# sch.net
KiCad netlist of a schematic drawn in Altium Designer
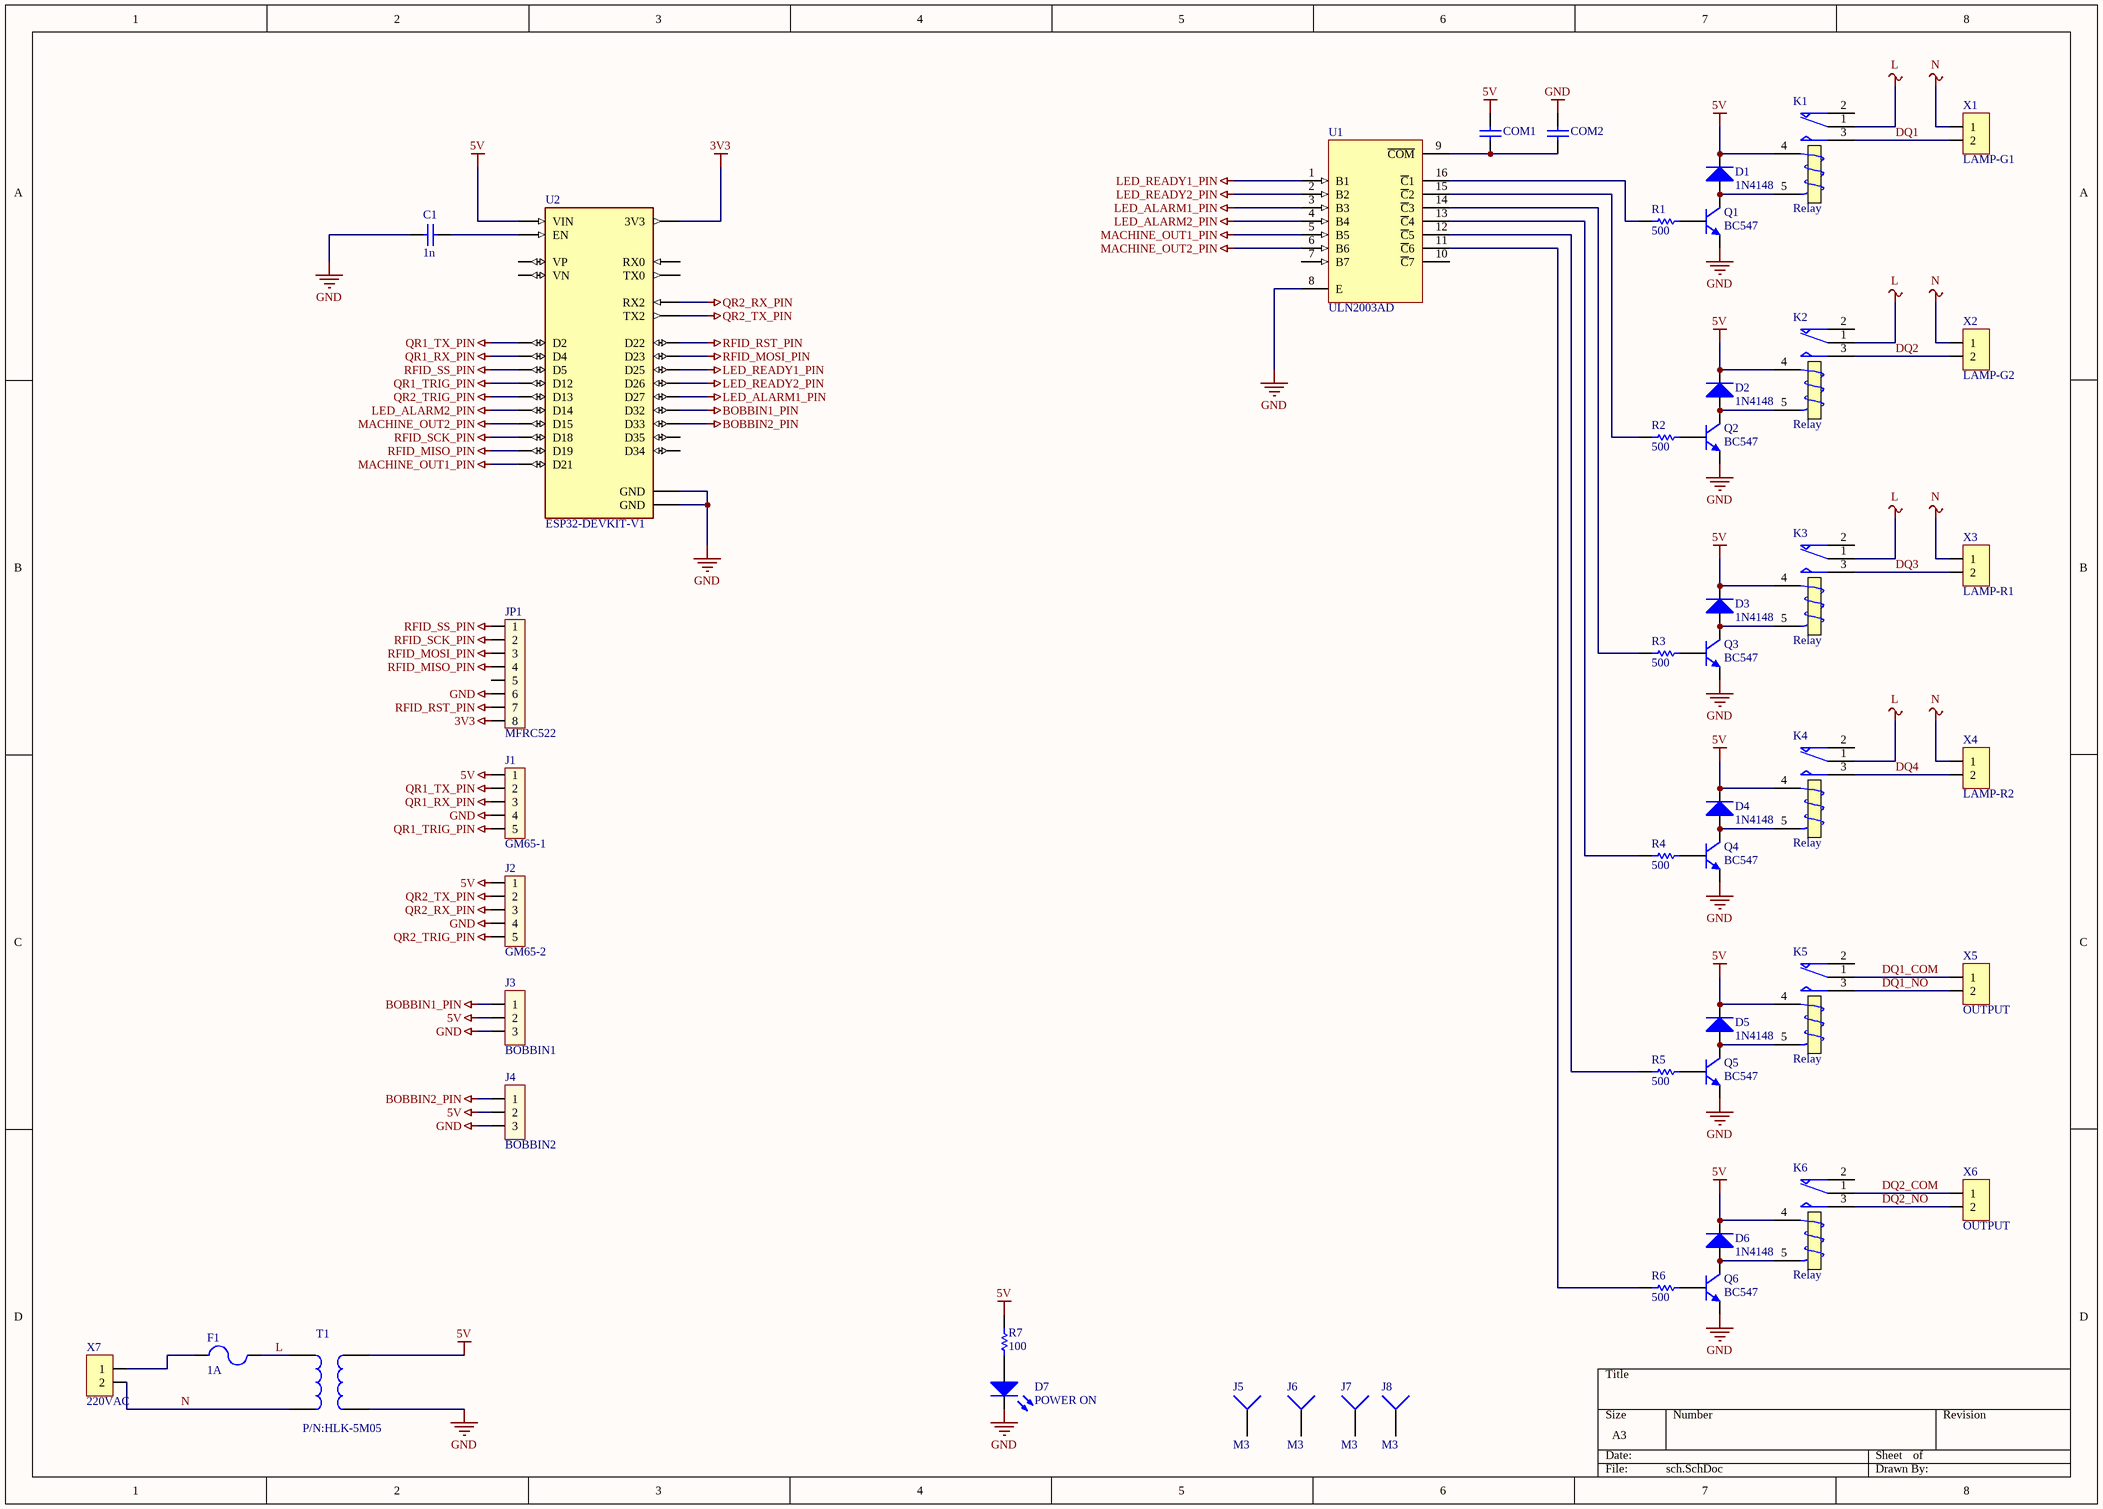
[diagram p0: sch.SchDoc]

(export (version "E")
  (design (tool "Eeschema 10.0.6"))
  (components
    (comp (ref "C1")
      (value "1n")
      (footprint "CR2012-0805")
      (description "Capacitor")
      (fields (field (name "PUBLISHER") "Altium Limited"))
      (libsource (lib "Miscellaneous Devices") (part "Cap"))
    )
    (comp (ref "COM1")
      (value "~")
      (footprint "CR2012-0805")
      (description "Capacitor")
      (fields (field (name "PUBLISHER") "Altium Limited"))
      (libsource (lib "Miscellaneous Devices") (part "Cap"))
    )
    (comp (ref "COM2")
      (value "~")
      (footprint "CR2012-0805")
      (description "Capacitor")
      (fields (field (name "PUBLISHER") "Altium Limited"))
      (libsource (lib "Miscellaneous Devices") (part "Cap"))
    )
    (comp (ref "D1")
      (value "1N4148")
      (footprint "D4148")
      (description "Default Diode")
      (fields (field (name "PUBLISHER") "Altium Limited"))
      (libsource (lib "weerachai") (part "Diode"))
    )
    (comp (ref "D2")
      (value "1N4148")
      (footprint "D4148")
      (description "Default Diode")
      (fields (field (name "PUBLISHER") "Altium Limited"))
      (libsource (lib "weerachai") (part "Diode"))
    )
    (comp (ref "D3")
      (value "1N4148")
      (footprint "D4148")
      (description "Default Diode")
      (fields (field (name "PUBLISHER") "Altium Limited"))
      (libsource (lib "weerachai") (part "Diode"))
    )
    (comp (ref "D4")
      (value "1N4148")
      (footprint "D4148")
      (description "Default Diode")
      (fields (field (name "PUBLISHER") "Altium Limited"))
      (libsource (lib "weerachai") (part "Diode"))
    )
    (comp (ref "D5")
      (value "1N4148")
      (footprint "D4148")
      (description "Default Diode")
      (fields (field (name "PUBLISHER") "Altium Limited"))
      (libsource (lib "weerachai") (part "Diode"))
    )
    (comp (ref "D6")
      (value "1N4148")
      (footprint "D4148")
      (description "Default Diode")
      (fields (field (name "PUBLISHER") "Altium Limited"))
      (libsource (lib "weerachai") (part "Diode"))
    )
    (comp (ref "D7")
      (value "POWER ON")
      (footprint "LED")
      (description "Typical INFRARED GaAs LED")
      (fields (field (name "PUBLISHER") "Altium Limited"))
      (libsource (lib "weerachai") (part "LED0"))
    )
    (comp (ref "F1")
      (value "1A")
      (footprint "CAP5W")
      (description "Fuse")
      (fields (field (name "PUBLISHER") "Altium Limited"))
      (libsource (lib "weerachai") (part "Fuse 2"))
    )
    (comp (ref "J1") (value "GM65-1") (footprint "XH2.54-5P") (libsource (lib "My Library") (part "JP5")))
    (comp (ref "J2") (value "GM65-2") (footprint "XH2.54-5P") (libsource (lib "My Library") (part "JP5")))
    (comp (ref "J3")
      (value "BOBBIN1")
      (footprint "XH2.54-3P")
      (description "Jumper 3")
      (libsource (lib "My Library") (part "JP3"))
    )
    (comp (ref "J4")
      (value "BOBBIN2")
      (footprint "XH2.54-3P")
      (description "Jumper 3")
      (libsource (lib "My Library") (part "JP3"))
    )
    (comp (ref "J5")
      (value "M3")
      (footprint "PAD")
      (description "Socket")
      (fields (field (name "PUBLISHER") "Altium Limited"))
      (libsource (lib "weerachai") (part "Socket"))
    )
    (comp (ref "J6")
      (value "M3")
      (footprint "PAD")
      (description "Socket")
      (fields (field (name "PUBLISHER") "Altium Limited"))
      (libsource (lib "weerachai") (part "Socket"))
    )
    (comp (ref "J7")
      (value "M3")
      (footprint "PAD")
      (description "Socket")
      (fields (field (name "PUBLISHER") "Altium Limited"))
      (libsource (lib "weerachai") (part "Socket"))
    )
    (comp (ref "J8")
      (value "M3")
      (footprint "PAD")
      (description "Socket")
      (fields (field (name "PUBLISHER") "Altium Limited"))
      (libsource (lib "weerachai") (part "Socket"))
    )
    (comp (ref "JP1")
      (value "MFRC522")
      (footprint "SIP8")
      (description "JP8 PIN")
      (libsource (lib "My Library") (part "JP8"))
    )
    (comp (ref "K1")
      (value "Relay")
      (footprint "RELAY1CON_REV")
      (description "SPDT Relay")
      (fields (field (name "PUBLISHER") "Altium Limited"))
      (libsource (lib "weerachai") (part "Relay"))
    )
    (comp (ref "K2")
      (value "Relay")
      (footprint "RELAY1CON_REV")
      (description "SPDT Relay")
      (fields (field (name "PUBLISHER") "Altium Limited"))
      (libsource (lib "weerachai") (part "Relay"))
    )
    (comp (ref "K3")
      (value "Relay")
      (footprint "RELAY1CON_REV")
      (description "SPDT Relay")
      (fields (field (name "PUBLISHER") "Altium Limited"))
      (libsource (lib "weerachai") (part "Relay"))
    )
    (comp (ref "K4")
      (value "Relay")
      (footprint "RELAY1CON_REV")
      (description "SPDT Relay")
      (fields (field (name "PUBLISHER") "Altium Limited"))
      (libsource (lib "weerachai") (part "Relay"))
    )
    (comp (ref "K5")
      (value "Relay")
      (footprint "RELAY1CON_REV")
      (description "SPDT Relay")
      (fields (field (name "PUBLISHER") "Altium Limited"))
      (libsource (lib "weerachai") (part "Relay"))
    )
    (comp (ref "K6")
      (value "Relay")
      (footprint "RELAY1CON_REV")
      (description "SPDT Relay")
      (fields (field (name "PUBLISHER") "Altium Limited"))
      (libsource (lib "weerachai") (part "Relay"))
    )
    (comp (ref "Q1")
      (value "BC547")
      (footprint "TO-92")
      (description "NPN General Purpose Amplifier")
      (fields (field (name "PUBLISHER") "Altium Limited"))
      (libsource (lib "weerachai") (part "2N3904"))
    )
    (comp (ref "Q2")
      (value "BC547")
      (footprint "TO-92")
      (description "NPN General Purpose Amplifier")
      (fields (field (name "PUBLISHER") "Altium Limited"))
      (libsource (lib "weerachai") (part "2N3904"))
    )
    (comp (ref "Q3")
      (value "BC547")
      (footprint "TO-92")
      (description "NPN General Purpose Amplifier")
      (fields (field (name "PUBLISHER") "Altium Limited"))
      (libsource (lib "weerachai") (part "2N3904"))
    )
    (comp (ref "Q4")
      (value "BC547")
      (footprint "TO-92")
      (description "NPN General Purpose Amplifier")
      (fields (field (name "PUBLISHER") "Altium Limited"))
      (libsource (lib "weerachai") (part "2N3904"))
    )
    (comp (ref "Q5")
      (value "BC547")
      (footprint "TO-92")
      (description "NPN General Purpose Amplifier")
      (fields (field (name "PUBLISHER") "Altium Limited"))
      (libsource (lib "weerachai") (part "2N3904"))
    )
    (comp (ref "Q6")
      (value "BC547")
      (footprint "TO-92")
      (description "NPN General Purpose Amplifier")
      (fields (field (name "PUBLISHER") "Altium Limited"))
      (libsource (lib "weerachai") (part "2N3904"))
    )
    (comp (ref "R1")
      (value "500")
      (footprint "R1/8")
      (description "Resistor")
      (fields (field (name "PUBLISHER") "Altium Limited"))
      (libsource (lib "weerachai") (part "Res1"))
    )
    (comp (ref "R2")
      (value "500")
      (footprint "R1/8")
      (description "Resistor")
      (fields (field (name "PUBLISHER") "Altium Limited"))
      (libsource (lib "weerachai") (part "Res1"))
    )
    (comp (ref "R3")
      (value "500")
      (footprint "R1/8")
      (description "Resistor")
      (fields (field (name "PUBLISHER") "Altium Limited"))
      (libsource (lib "weerachai") (part "Res1"))
    )
    (comp (ref "R4")
      (value "500")
      (footprint "R1/8")
      (description "Resistor")
      (fields (field (name "PUBLISHER") "Altium Limited"))
      (libsource (lib "weerachai") (part "Res1"))
    )
    (comp (ref "R5")
      (value "500")
      (footprint "R1/8")
      (description "Resistor")
      (fields (field (name "PUBLISHER") "Altium Limited"))
      (libsource (lib "weerachai") (part "Res1"))
    )
    (comp (ref "R6")
      (value "500")
      (footprint "R1/8")
      (description "Resistor")
      (fields (field (name "PUBLISHER") "Altium Limited"))
      (libsource (lib "weerachai") (part "Res1"))
    )
    (comp (ref "R7")
      (value "100")
      (footprint "R1/8")
      (description "Resistor")
      (fields (field (name "PUBLISHER") "Altium Limited"))
      (libsource (lib "weerachai") (part "Res1"))
    )
    (comp (ref "T1")
      (value "P/N:HLK-5M05")
      (footprint "HLK-PM01")
      (description "Transformer")
      (fields (field (name "PUBLISHER") "Altium Limited"))
      (libsource (lib "weerachai") (part "Trans"))
    )
    (comp (ref "U1")
      (value "ULN2003AD")
      (footprint "D016_N")
      (description "Darlington Transistor Array")
      (fields (field (name "PUBLISHER") "Altium Limited"))
      (libsource (lib "TI Interface Darlington Driver") (part "ULN2003AD"))
    )
    (comp (ref "U2")
      (value "ESP32-DEVKIT-V1")
      (footprint "ESP32-30PIN")
      (libsource (lib "weerachai") (part "ESP32-DEVKIT-V1"))
    )
    (comp (ref "X1")
      (value "LAMP-G1")
      (footprint "KF142V-5.08-P2")
      (description "WR-PHD 2.54 mm Angled Socket Header")
      (fields
        (field (name "MANUFACTURER") "Würth Elektronik eiSos GmbH")
        (field (name "PARTNO") "613002143121")
        (field (name "CREATED BY") "Karrer Zheng")
      )
      (libsource (lib "My Library") (part "JP2"))
    )
    (comp (ref "X2")
      (value "LAMP-G2")
      (footprint "KF142V-5.08-P2")
      (description "WR-PHD 2.54 mm Angled Socket Header")
      (fields
        (field (name "MANUFACTURER") "Würth Elektronik eiSos GmbH")
        (field (name "PARTNO") "613002143121")
        (field (name "CREATED BY") "Karrer Zheng")
      )
      (libsource (lib "My Library") (part "JP2"))
    )
    (comp (ref "X3")
      (value "LAMP-R1")
      (footprint "KF142V-5.08-P2")
      (description "WR-PHD 2.54 mm Angled Socket Header")
      (fields
        (field (name "MANUFACTURER") "Würth Elektronik eiSos GmbH")
        (field (name "PARTNO") "613002143121")
        (field (name "CREATED BY") "Karrer Zheng")
      )
      (libsource (lib "My Library") (part "JP2"))
    )
    (comp (ref "X4")
      (value "LAMP-R2")
      (footprint "KF142V-5.08-P2")
      (description "WR-PHD 2.54 mm Angled Socket Header")
      (fields
        (field (name "MANUFACTURER") "Würth Elektronik eiSos GmbH")
        (field (name "PARTNO") "613002143121")
        (field (name "CREATED BY") "Karrer Zheng")
      )
      (libsource (lib "My Library") (part "JP2"))
    )
    (comp (ref "X5")
      (value "OUTPUT")
      (footprint "KF142V-5.08-P2")
      (description "WR-PHD 2.54 mm Angled Socket Header")
      (fields
        (field (name "MANUFACTURER") "Würth Elektronik eiSos GmbH")
        (field (name "PARTNO") "613002143121")
        (field (name "CREATED BY") "Karrer Zheng")
      )
      (libsource (lib "My Library") (part "JP2"))
    )
    (comp (ref "X6")
      (value "OUTPUT")
      (footprint "KF142V-5.08-P2")
      (description "WR-PHD 2.54 mm Angled Socket Header")
      (fields
        (field (name "MANUFACTURER") "Würth Elektronik eiSos GmbH")
        (field (name "PARTNO") "613002143121")
        (field (name "CREATED BY") "Karrer Zheng")
      )
      (libsource (lib "My Library") (part "JP2"))
    )
    (comp (ref "X7")
      (value "220VAC")
      (footprint "KF142V-5.08-P2")
      (description "WR-PHD 2.54 mm Angled Socket Header")
      (fields
        (field (name "MANUFACTURER") "Würth Elektronik eiSos GmbH")
        (field (name "PARTNO") "613002143121")
        (field (name "CREATED BY") "Karrer Zheng")
      )
      (libsource (lib "") (part "JP2_1"))
    )
  )
  (nets
    (net (code "1") (name "/DQ1") (class "Default")
      (node (ref "K1") (pin "3") (pinfunction "NO_3") (pintype "passive"))
      (node (ref "X1") (pin "2") (pinfunction "2_2") (pintype "passive"))
    )
    (net (code "2") (name "/DQ1_COM") (class "Default")
      (node (ref "K5") (pin "1") (pinfunction "COM_1") (pintype "passive"))
      (node (ref "X5") (pin "1") (pinfunction "1_1") (pintype "passive"))
    )
    (net (code "3") (name "/DQ1_NO") (class "Default")
      (node (ref "K5") (pin "3") (pinfunction "NO_3") (pintype "passive"))
      (node (ref "X5") (pin "2") (pinfunction "2_2") (pintype "passive"))
    )
    (net (code "4") (name "/DQ2") (class "Default")
      (node (ref "K2") (pin "3") (pinfunction "NO_3") (pintype "passive"))
      (node (ref "X2") (pin "2") (pinfunction "2_2") (pintype "passive"))
    )
    (net (code "5") (name "/DQ2_COM") (class "Default")
      (node (ref "K6") (pin "1") (pinfunction "COM_1") (pintype "passive"))
      (node (ref "X6") (pin "1") (pinfunction "1_1") (pintype "passive"))
    )
    (net (code "6") (name "/DQ2_NO") (class "Default")
      (node (ref "K6") (pin "3") (pinfunction "NO_3") (pintype "passive"))
      (node (ref "X6") (pin "2") (pinfunction "2_2") (pintype "passive"))
    )
    (net (code "7") (name "/DQ3") (class "Default")
      (node (ref "K3") (pin "3") (pinfunction "NO_3") (pintype "passive"))
      (node (ref "X3") (pin "2") (pinfunction "2_2") (pintype "passive"))
    )
    (net (code "8") (name "/DQ4") (class "Default")
      (node (ref "K4") (pin "3") (pinfunction "NO_3") (pintype "passive"))
      (node (ref "X4") (pin "2") (pinfunction "2_2") (pintype "passive"))
    )
    (net (code "9") (name "3V3") (class "Default")
      (node (ref "JP1") (pin "8") (pinfunction "8_8") (pintype "passive"))
      (node (ref "U2") (pin "1") (pinfunction "3V3_1") (pintype "output"))
    )
    (net (code "10") (name "5V") (class "Default")
      (node (ref "COM1") (pin "2") (pinfunction "2_2") (pintype "passive"))
      (node (ref "D1") (pin "K") (pinfunction "K_K") (pintype "passive"))
      (node (ref "D2") (pin "K") (pinfunction "K_K") (pintype "passive"))
      (node (ref "D3") (pin "K") (pinfunction "K_K") (pintype "passive"))
      (node (ref "D4") (pin "K") (pinfunction "K_K") (pintype "passive"))
      (node (ref "D5") (pin "K") (pinfunction "K_K") (pintype "passive"))
      (node (ref "D6") (pin "K") (pinfunction "K_K") (pintype "passive"))
      (node (ref "J1") (pin "1") (pinfunction "1_1") (pintype "passive"))
      (node (ref "J2") (pin "1") (pinfunction "1_1") (pintype "passive"))
      (node (ref "J3") (pin "2") (pinfunction "2_2") (pintype "passive"))
      (node (ref "J4") (pin "2") (pinfunction "2_2") (pintype "passive"))
      (node (ref "K1") (pin "4") (pinfunction "T1_4") (pintype "passive"))
      (node (ref "K2") (pin "4") (pinfunction "T1_4") (pintype "passive"))
      (node (ref "K3") (pin "4") (pinfunction "T1_4") (pintype "passive"))
      (node (ref "K4") (pin "4") (pinfunction "T1_4") (pintype "passive"))
      (node (ref "K5") (pin "4") (pinfunction "T1_4") (pintype "passive"))
      (node (ref "K6") (pin "4") (pinfunction "T1_4") (pintype "passive"))
      (node (ref "R7") (pin "1") (pinfunction "1_1") (pintype "passive"))
      (node (ref "T1") (pin "4") (pinfunction "4_4") (pintype "passive"))
      (node (ref "U2") (pin "30") (pinfunction "VIN_30") (pintype "input"))
    )
    (net (code "11") (name "BOBBIN1_PIN") (class "Default")
      (node (ref "J3") (pin "1") (pinfunction "1_1") (pintype "passive"))
      (node (ref "U2") (pin "21") (pinfunction "D32_21") (pintype "bidirectional"))
    )
    (net (code "12") (name "BOBBIN2_PIN") (class "Default")
      (node (ref "J4") (pin "1") (pinfunction "1_1") (pintype "passive"))
      (node (ref "U2") (pin "22") (pinfunction "D33_22") (pintype "bidirectional"))
    )
    (net (code "13") (name "GND") (class "Default")
      (node (ref "C1") (pin "1") (pinfunction "1_1") (pintype "passive"))
      (node (ref "COM2") (pin "2") (pinfunction "2_2") (pintype "passive"))
      (node (ref "D7") (pin "2") (pinfunction "K_2") (pintype "passive"))
      (node (ref "J1") (pin "4") (pinfunction "4_4") (pintype "passive"))
      (node (ref "J2") (pin "4") (pinfunction "4_4") (pintype "passive"))
      (node (ref "J3") (pin "3") (pinfunction "3_3") (pintype "passive"))
      (node (ref "J4") (pin "3") (pinfunction "3_3") (pintype "passive"))
      (node (ref "JP1") (pin "6") (pinfunction "6_6") (pintype "passive"))
      (node (ref "Q1") (pin "3") (pinfunction "E_3") (pintype "passive"))
      (node (ref "Q2") (pin "3") (pinfunction "E_3") (pintype "passive"))
      (node (ref "Q3") (pin "3") (pinfunction "E_3") (pintype "passive"))
      (node (ref "Q4") (pin "3") (pinfunction "E_3") (pintype "passive"))
      (node (ref "Q5") (pin "3") (pinfunction "E_3") (pintype "passive"))
      (node (ref "Q6") (pin "3") (pinfunction "E_3") (pintype "passive"))
      (node (ref "T1") (pin "3") (pinfunction "3_3") (pintype "passive"))
      (node (ref "U1") (pin "8") (pinfunction "E_8") (pintype "power_in"))
      (node (ref "U2") (pin "2") (pinfunction "GND_2") (pintype "power_in"))
      (node (ref "U2") (pin "29") (pinfunction "GND_29") (pintype "power_in"))
    )
    (net (code "14") (name "L") (class "Default")
      (node (ref "F1") (pin "2") (pinfunction "2_2") (pintype "passive"))
      (node (ref "K1") (pin "1") (pinfunction "COM_1") (pintype "passive"))
      (node (ref "K2") (pin "1") (pinfunction "COM_1") (pintype "passive"))
      (node (ref "K3") (pin "1") (pinfunction "COM_1") (pintype "passive"))
      (node (ref "K4") (pin "1") (pinfunction "COM_1") (pintype "passive"))
      (node (ref "T1") (pin "2") (pinfunction "2_2") (pintype "passive"))
    )
    (net (code "15") (name "LED_ALARM1_PIN") (class "Default")
      (node (ref "U1") (pin "3") (pinfunction "B3_3") (pintype "input"))
      (node (ref "U2") (pin "25") (pinfunction "D27_25") (pintype "bidirectional"))
    )
    (net (code "16") (name "LED_ALARM2_PIN") (class "Default")
      (node (ref "U1") (pin "4") (pinfunction "B4_4") (pintype "input"))
      (node (ref "U2") (pin "26") (pinfunction "D14_26") (pintype "bidirectional"))
    )
    (net (code "17") (name "LED_READY1_PIN") (class "Default")
      (node (ref "U1") (pin "1") (pinfunction "B1_1") (pintype "input"))
      (node (ref "U2") (pin "23") (pinfunction "D25_23") (pintype "bidirectional"))
    )
    (net (code "18") (name "LED_READY2_PIN") (class "Default")
      (node (ref "U1") (pin "2") (pinfunction "B2_2") (pintype "input"))
      (node (ref "U2") (pin "24") (pinfunction "D26_24") (pintype "bidirectional"))
    )
    (net (code "19") (name "MACHINE_OUT1_PIN") (class "Default")
      (node (ref "U1") (pin "5") (pinfunction "B5_5") (pintype "input"))
      (node (ref "U2") (pin "11") (pinfunction "D21_11") (pintype "bidirectional"))
    )
    (net (code "20") (name "MACHINE_OUT2_PIN") (class "Default")
      (node (ref "U1") (pin "6") (pinfunction "B6_6") (pintype "input"))
      (node (ref "U2") (pin "3") (pinfunction "D15_3") (pintype "bidirectional"))
    )
    (net (code "21") (name "N") (class "Default")
      (node (ref "T1") (pin "1") (pinfunction "1_1") (pintype "passive"))
      (node (ref "X1") (pin "1") (pinfunction "1_1") (pintype "passive"))
      (node (ref "X2") (pin "1") (pinfunction "1_1") (pintype "passive"))
      (node (ref "X3") (pin "1") (pinfunction "1_1") (pintype "passive"))
      (node (ref "X4") (pin "1") (pinfunction "1_1") (pintype "passive"))
      (node (ref "X7") (pin "2") (pinfunction "2_2") (pintype "passive"))
    )
    (net (code "22") (name "Net-(D7-A)") (class "Default")
      (node (ref "D7") (pin "1") (pinfunction "A_1") (pintype "passive"))
      (node (ref "R7") (pin "2") (pinfunction "2_2") (pintype "passive"))
    )
    (net (code "23") (name "Net-(F1-Pad1)") (class "Default")
      (node (ref "F1") (pin "1") (pinfunction "1_1") (pintype "passive"))
      (node (ref "X7") (pin "1") (pinfunction "1_1") (pintype "passive"))
    )
    (net (code "24") (name "Net-(K1-T2)") (class "Default")
      (node (ref "D1") (pin "A") (pinfunction "A_A") (pintype "passive"))
      (node (ref "K1") (pin "5") (pinfunction "T2_5") (pintype "passive"))
      (node (ref "Q1") (pin "1") (pinfunction "C_1") (pintype "passive"))
    )
    (net (code "25") (name "Net-(K2-T2)") (class "Default")
      (node (ref "D2") (pin "A") (pinfunction "A_A") (pintype "passive"))
      (node (ref "K2") (pin "5") (pinfunction "T2_5") (pintype "passive"))
      (node (ref "Q2") (pin "1") (pinfunction "C_1") (pintype "passive"))
    )
    (net (code "26") (name "Net-(K3-T2)") (class "Default")
      (node (ref "D3") (pin "A") (pinfunction "A_A") (pintype "passive"))
      (node (ref "K3") (pin "5") (pinfunction "T2_5") (pintype "passive"))
      (node (ref "Q3") (pin "1") (pinfunction "C_1") (pintype "passive"))
    )
    (net (code "27") (name "Net-(K4-T2)") (class "Default")
      (node (ref "D4") (pin "A") (pinfunction "A_A") (pintype "passive"))
      (node (ref "K4") (pin "5") (pinfunction "T2_5") (pintype "passive"))
      (node (ref "Q4") (pin "1") (pinfunction "C_1") (pintype "passive"))
    )
    (net (code "28") (name "Net-(K5-T2)") (class "Default")
      (node (ref "D5") (pin "A") (pinfunction "A_A") (pintype "passive"))
      (node (ref "K5") (pin "5") (pinfunction "T2_5") (pintype "passive"))
      (node (ref "Q5") (pin "1") (pinfunction "C_1") (pintype "passive"))
    )
    (net (code "29") (name "Net-(K6-T2)") (class "Default")
      (node (ref "D6") (pin "A") (pinfunction "A_A") (pintype "passive"))
      (node (ref "K6") (pin "5") (pinfunction "T2_5") (pintype "passive"))
      (node (ref "Q6") (pin "1") (pinfunction "C_1") (pintype "passive"))
    )
    (net (code "30") (name "Net-(Q1-B)") (class "Default")
      (node (ref "Q1") (pin "2") (pinfunction "B_2") (pintype "passive"))
      (node (ref "R1") (pin "1") (pinfunction "1_1") (pintype "passive"))
    )
    (net (code "31") (name "Net-(Q2-B)") (class "Default")
      (node (ref "Q2") (pin "2") (pinfunction "B_2") (pintype "passive"))
      (node (ref "R2") (pin "1") (pinfunction "1_1") (pintype "passive"))
    )
    (net (code "32") (name "Net-(Q3-B)") (class "Default")
      (node (ref "Q3") (pin "2") (pinfunction "B_2") (pintype "passive"))
      (node (ref "R3") (pin "1") (pinfunction "1_1") (pintype "passive"))
    )
    (net (code "33") (name "Net-(Q4-B)") (class "Default")
      (node (ref "Q4") (pin "2") (pinfunction "B_2") (pintype "passive"))
      (node (ref "R4") (pin "1") (pinfunction "1_1") (pintype "passive"))
    )
    (net (code "34") (name "Net-(Q5-B)") (class "Default")
      (node (ref "Q5") (pin "2") (pinfunction "B_2") (pintype "passive"))
      (node (ref "R5") (pin "1") (pinfunction "1_1") (pintype "passive"))
    )
    (net (code "35") (name "Net-(Q6-B)") (class "Default")
      (node (ref "Q6") (pin "2") (pinfunction "B_2") (pintype "passive"))
      (node (ref "R6") (pin "1") (pinfunction "1_1") (pintype "passive"))
    )
    (net (code "36") (name "Net-(U1-~{COM})") (class "Default")
      (node (ref "COM1") (pin "1") (pinfunction "1_1") (pintype "passive"))
      (node (ref "COM2") (pin "1") (pinfunction "1_1") (pintype "passive"))
      (node (ref "U1") (pin "9") (pinfunction "~{COM}_9") (pintype "passive"))
    )
    (net (code "37") (name "Net-(U1-~{C}1)") (class "Default")
      (node (ref "R1") (pin "2") (pinfunction "2_2") (pintype "passive"))
      (node (ref "U1") (pin "16") (pinfunction "~{C}1_16") (pintype "open_collector"))
    )
    (net (code "38") (name "Net-(U1-~{C}2)") (class "Default")
      (node (ref "R2") (pin "2") (pinfunction "2_2") (pintype "passive"))
      (node (ref "U1") (pin "15") (pinfunction "~{C}2_15") (pintype "open_collector"))
    )
    (net (code "39") (name "Net-(U1-~{C}3)") (class "Default")
      (node (ref "R3") (pin "2") (pinfunction "2_2") (pintype "passive"))
      (node (ref "U1") (pin "14") (pinfunction "~{C}3_14") (pintype "open_collector"))
    )
    (net (code "40") (name "Net-(U1-~{C}4)") (class "Default")
      (node (ref "R4") (pin "2") (pinfunction "2_2") (pintype "passive"))
      (node (ref "U1") (pin "13") (pinfunction "~{C}4_13") (pintype "open_collector"))
    )
    (net (code "41") (name "Net-(U1-~{C}5)") (class "Default")
      (node (ref "R5") (pin "2") (pinfunction "2_2") (pintype "passive"))
      (node (ref "U1") (pin "12") (pinfunction "~{C}5_12") (pintype "open_collector"))
    )
    (net (code "42") (name "Net-(U1-~{C}6)") (class "Default")
      (node (ref "R6") (pin "2") (pinfunction "2_2") (pintype "passive"))
      (node (ref "U1") (pin "11") (pinfunction "~{C}6_11") (pintype "open_collector"))
    )
    (net (code "43") (name "Net-(U2-EN)") (class "Default")
      (node (ref "C1") (pin "2") (pinfunction "2_2") (pintype "passive"))
      (node (ref "U2") (pin "16") (pinfunction "EN_16") (pintype "input"))
    )
    (net (code "44") (name "QR1_RX_PIN") (class "Default")
      (node (ref "J1") (pin "3") (pinfunction "3_3") (pintype "passive"))
      (node (ref "U2") (pin "5") (pinfunction "D4_5") (pintype "bidirectional"))
    )
    (net (code "45") (name "QR1_TRIG_PIN") (class "Default")
      (node (ref "J1") (pin "5") (pinfunction "5_5") (pintype "passive"))
      (node (ref "U2") (pin "27") (pinfunction "D12_27") (pintype "bidirectional"))
    )
    (net (code "46") (name "QR1_TX_PIN") (class "Default")
      (node (ref "J1") (pin "2") (pinfunction "2_2") (pintype "passive"))
      (node (ref "U2") (pin "4") (pinfunction "D2_4") (pintype "bidirectional"))
    )
    (net (code "47") (name "QR2_RX_PIN") (class "Default")
      (node (ref "J2") (pin "3") (pinfunction "3_3") (pintype "passive"))
      (node (ref "U2") (pin "6") (pinfunction "RX2_6") (pintype "input"))
    )
    (net (code "48") (name "QR2_TRIG_PIN") (class "Default")
      (node (ref "J2") (pin "5") (pinfunction "5_5") (pintype "passive"))
      (node (ref "U2") (pin "28") (pinfunction "D13_28") (pintype "bidirectional"))
    )
    (net (code "49") (name "QR2_TX_PIN") (class "Default")
      (node (ref "J2") (pin "2") (pinfunction "2_2") (pintype "passive"))
      (node (ref "U2") (pin "7") (pinfunction "TX2_7") (pintype "output"))
    )
    (net (code "50") (name "RFID_MISO_PIN") (class "Default")
      (node (ref "JP1") (pin "4") (pinfunction "4_4") (pintype "passive"))
      (node (ref "U2") (pin "10") (pinfunction "D19_10") (pintype "bidirectional"))
    )
    (net (code "51") (name "RFID_MOSI_PIN") (class "Default")
      (node (ref "JP1") (pin "3") (pinfunction "3_3") (pintype "passive"))
      (node (ref "U2") (pin "15") (pinfunction "D23_15") (pintype "bidirectional"))
    )
    (net (code "52") (name "RFID_RST_PIN") (class "Default")
      (node (ref "JP1") (pin "7") (pinfunction "7_7") (pintype "passive"))
      (node (ref "U2") (pin "14") (pinfunction "D22_14") (pintype "bidirectional"))
    )
    (net (code "53") (name "RFID_SCK_PIN") (class "Default")
      (node (ref "JP1") (pin "2") (pinfunction "2_2") (pintype "passive"))
      (node (ref "U2") (pin "9") (pinfunction "D18_9") (pintype "bidirectional"))
    )
    (net (code "54") (name "RFID_SS_PIN") (class "Default")
      (node (ref "JP1") (pin "1") (pinfunction "1_1") (pintype "passive"))
      (node (ref "U2") (pin "8") (pinfunction "D5_8") (pintype "bidirectional"))
    )
    (net (code "55") (name "unconnected-(J5-Pad1)") (class "Default")
      (node (ref "J5") (pin "1") (pinfunction "1_1") (pintype "passive"))
    )
    (net (code "56") (name "unconnected-(J6-Pad1)") (class "Default")
      (node (ref "J6") (pin "1") (pinfunction "1_1") (pintype "passive"))
    )
    (net (code "57") (name "unconnected-(J7-Pad1)") (class "Default")
      (node (ref "J7") (pin "1") (pinfunction "1_1") (pintype "passive"))
    )
    (net (code "58") (name "unconnected-(J8-Pad1)") (class "Default")
      (node (ref "J8") (pin "1") (pinfunction "1_1") (pintype "passive"))
    )
    (net (code "59") (name "unconnected-(JP1-Pad5)") (class "Default")
      (node (ref "JP1") (pin "5") (pinfunction "5_5") (pintype "passive"))
    )
    (net (code "60") (name "unconnected-(K1-NC-Pad2)") (class "Default")
      (node (ref "K1") (pin "2") (pinfunction "NC_2") (pintype "passive"))
    )
    (net (code "61") (name "unconnected-(K2-NC-Pad2)") (class "Default")
      (node (ref "K2") (pin "2") (pinfunction "NC_2") (pintype "passive"))
    )
    (net (code "62") (name "unconnected-(K3-NC-Pad2)") (class "Default")
      (node (ref "K3") (pin "2") (pinfunction "NC_2") (pintype "passive"))
    )
    (net (code "63") (name "unconnected-(K4-NC-Pad2)") (class "Default")
      (node (ref "K4") (pin "2") (pinfunction "NC_2") (pintype "passive"))
    )
    (net (code "64") (name "unconnected-(K5-NC-Pad2)") (class "Default")
      (node (ref "K5") (pin "2") (pinfunction "NC_2") (pintype "passive"))
    )
    (net (code "65") (name "unconnected-(K6-NC-Pad2)") (class "Default")
      (node (ref "K6") (pin "2") (pinfunction "NC_2") (pintype "passive"))
    )
    (net (code "66") (name "unconnected-(U1-B7-Pad7)") (class "Default")
      (node (ref "U1") (pin "7") (pinfunction "B7_7") (pintype "input"))
    )
    (net (code "67") (name "unconnected-(U1-~{C}7-Pad10)") (class "Default")
      (node (ref "U1") (pin "10") (pinfunction "~{C}7_10") (pintype "open_collector"))
    )
    (net (code "68") (name "unconnected-(U2-D34-Pad19)") (class "Default")
      (node (ref "U2") (pin "19") (pinfunction "D34_19") (pintype "bidirectional"))
    )
    (net (code "69") (name "unconnected-(U2-D35-Pad20)") (class "Default")
      (node (ref "U2") (pin "20") (pinfunction "D35_20") (pintype "bidirectional"))
    )
    (net (code "70") (name "unconnected-(U2-RX0-Pad12)") (class "Default")
      (node (ref "U2") (pin "12") (pinfunction "RX0_12") (pintype "input"))
    )
    (net (code "71") (name "unconnected-(U2-TX0-Pad13)") (class "Default")
      (node (ref "U2") (pin "13") (pinfunction "TX0_13") (pintype "output"))
    )
    (net (code "72") (name "unconnected-(U2-VN-Pad18)") (class "Default")
      (node (ref "U2") (pin "18") (pinfunction "VN_18") (pintype "bidirectional"))
    )
    (net (code "73") (name "unconnected-(U2-VP-Pad17)") (class "Default")
      (node (ref "U2") (pin "17") (pinfunction "VP_17") (pintype "bidirectional"))
    )
  )
)
